# FlyballETS-SENSORS.net
KiCad netlist of a schematic drawn in EAGLE
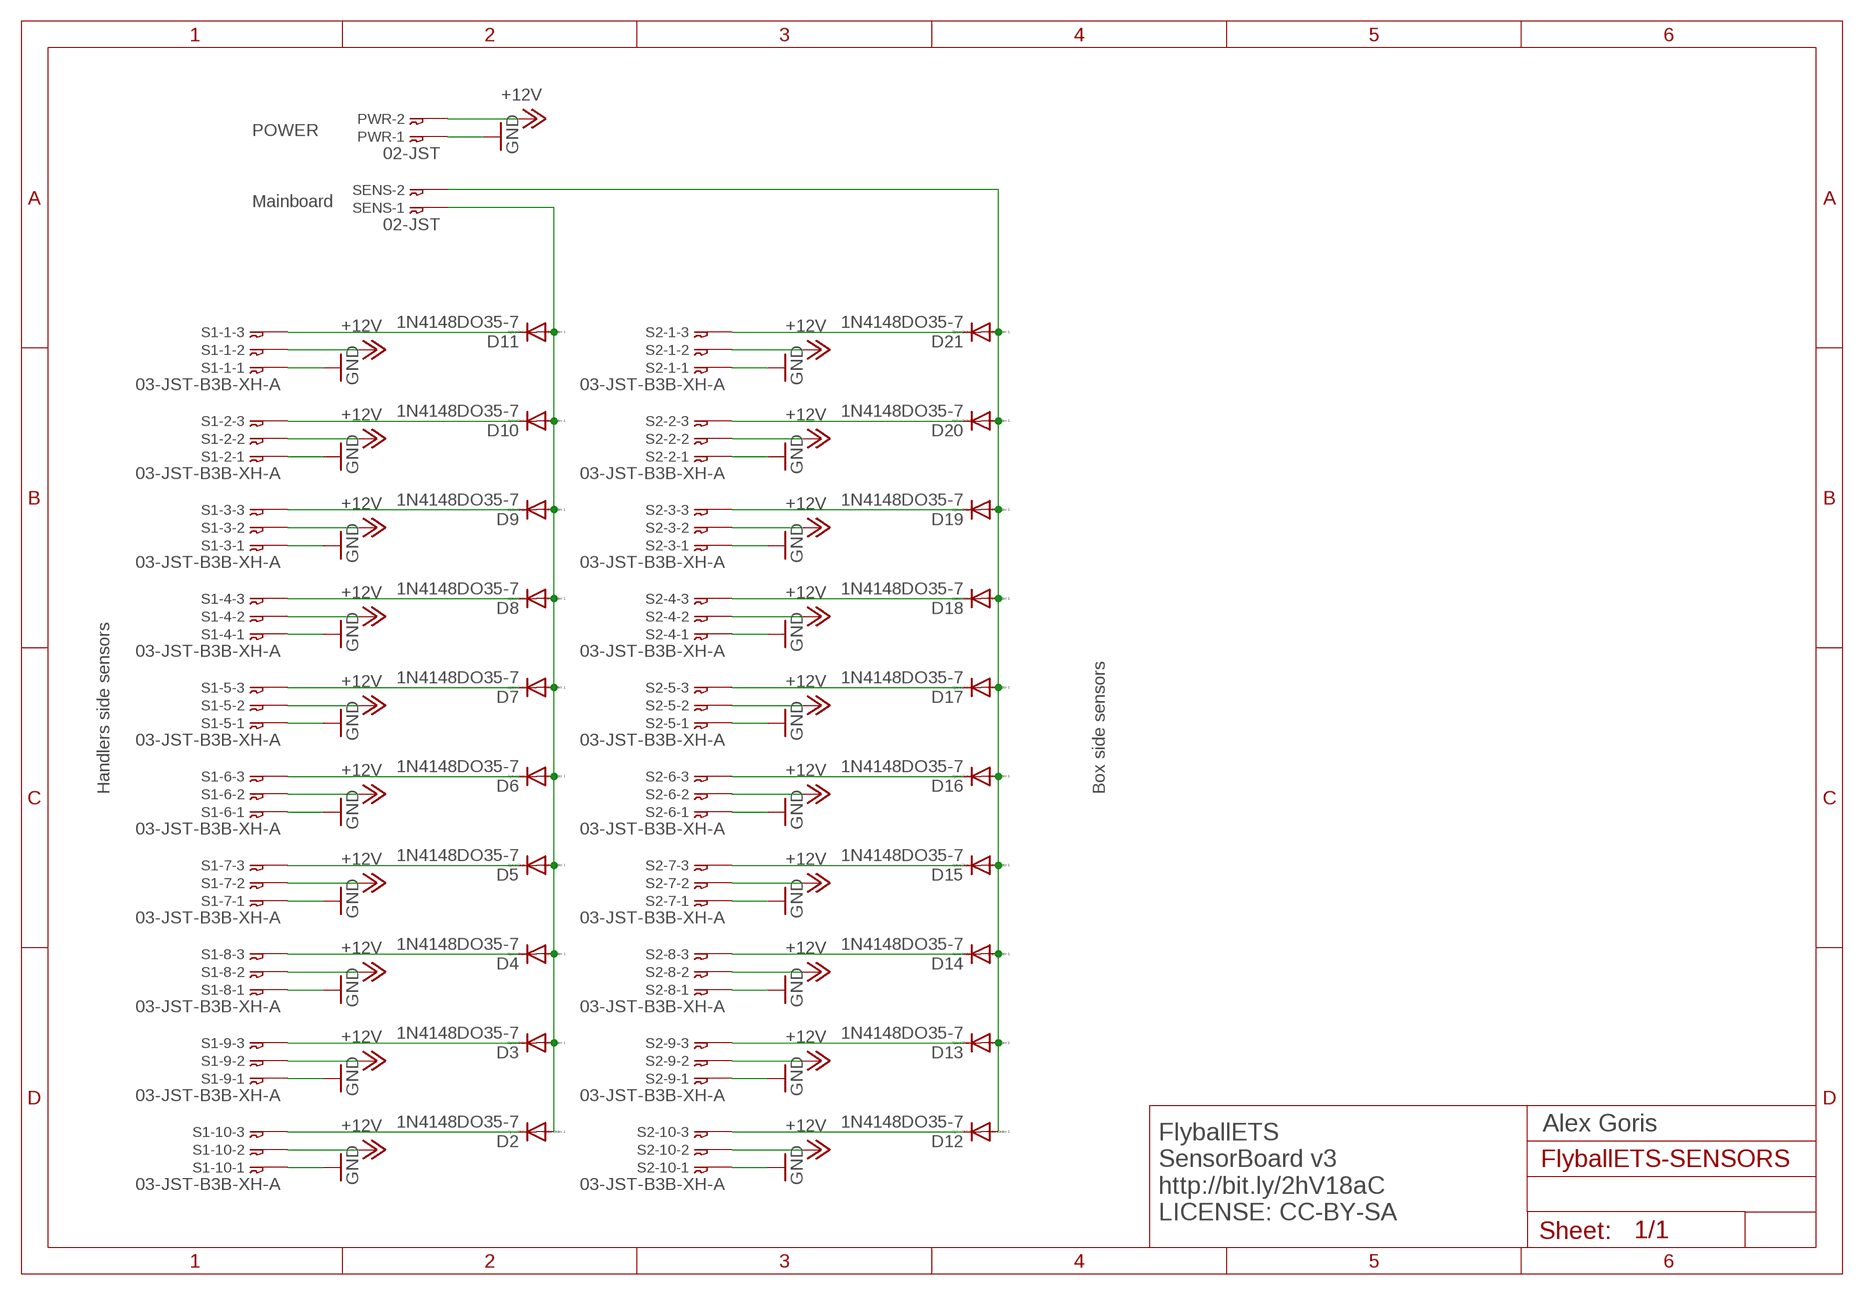
[diagram p0: schematic, sheet 1]

(export (version "E")
  (design (tool "Eeschema 10.0.6"))
  (components
    (comp (ref "D2")
      (value "1N4148DO35-7")
      (footprint "eagle-import:DO35-7")
      (libsource (lib "eagle-import") (part "1N4148DO35-7"))
    )
    (comp (ref "D3")
      (value "1N4148DO35-7")
      (footprint "eagle-import:DO35-7")
      (libsource (lib "eagle-import") (part "1N4148DO35-7"))
    )
    (comp (ref "D4")
      (value "1N4148DO35-7")
      (footprint "eagle-import:DO35-7")
      (libsource (lib "eagle-import") (part "1N4148DO35-7"))
    )
    (comp (ref "D5")
      (value "1N4148DO35-7")
      (footprint "eagle-import:DO35-7")
      (libsource (lib "eagle-import") (part "1N4148DO35-7"))
    )
    (comp (ref "D6")
      (value "1N4148DO35-7")
      (footprint "eagle-import:DO35-7")
      (libsource (lib "eagle-import") (part "1N4148DO35-7"))
    )
    (comp (ref "D7")
      (value "1N4148DO35-7")
      (footprint "eagle-import:DO35-7")
      (libsource (lib "eagle-import") (part "1N4148DO35-7"))
    )
    (comp (ref "D8")
      (value "1N4148DO35-7")
      (footprint "eagle-import:DO35-7")
      (libsource (lib "eagle-import") (part "1N4148DO35-7"))
    )
    (comp (ref "D9")
      (value "1N4148DO35-7")
      (footprint "eagle-import:DO35-7")
      (libsource (lib "eagle-import") (part "1N4148DO35-7"))
    )
    (comp (ref "D10")
      (value "1N4148DO35-7")
      (footprint "eagle-import:DO35-7")
      (libsource (lib "eagle-import") (part "1N4148DO35-7"))
    )
    (comp (ref "D11")
      (value "1N4148DO35-7")
      (footprint "eagle-import:DO35-7")
      (libsource (lib "eagle-import") (part "1N4148DO35-7"))
    )
    (comp (ref "D12")
      (value "1N4148DO35-7")
      (footprint "eagle-import:DO35-7")
      (libsource (lib "eagle-import") (part "1N4148DO35-7"))
    )
    (comp (ref "D13")
      (value "1N4148DO35-7")
      (footprint "eagle-import:DO35-7")
      (libsource (lib "eagle-import") (part "1N4148DO35-7"))
    )
    (comp (ref "D14")
      (value "1N4148DO35-7")
      (footprint "eagle-import:DO35-7")
      (libsource (lib "eagle-import") (part "1N4148DO35-7"))
    )
    (comp (ref "D15")
      (value "1N4148DO35-7")
      (footprint "eagle-import:DO35-7")
      (libsource (lib "eagle-import") (part "1N4148DO35-7"))
    )
    (comp (ref "D16")
      (value "1N4148DO35-7")
      (footprint "eagle-import:DO35-7")
      (libsource (lib "eagle-import") (part "1N4148DO35-7"))
    )
    (comp (ref "D17")
      (value "1N4148DO35-7")
      (footprint "eagle-import:DO35-7")
      (libsource (lib "eagle-import") (part "1N4148DO35-7"))
    )
    (comp (ref "D18")
      (value "1N4148DO35-7")
      (footprint "eagle-import:DO35-7")
      (libsource (lib "eagle-import") (part "1N4148DO35-7"))
    )
    (comp (ref "D19")
      (value "1N4148DO35-7")
      (footprint "eagle-import:DO35-7")
      (libsource (lib "eagle-import") (part "1N4148DO35-7"))
    )
    (comp (ref "D20")
      (value "1N4148DO35-7")
      (footprint "eagle-import:DO35-7")
      (libsource (lib "eagle-import") (part "1N4148DO35-7"))
    )
    (comp (ref "D21")
      (value "1N4148DO35-7")
      (footprint "eagle-import:DO35-7")
      (libsource (lib "eagle-import") (part "1N4148DO35-7"))
    )
    (comp (ref "PWR")
      (value "02-JST")
      (footprint "eagle-import:B2B-XH")
      (libsource (lib "eagle-import") (part "02-JST"))
    )
    (comp (ref "S1-1")
      (value "03-JST-B3B-XH-A")
      (footprint "eagle-import:B3B-XH")
      (libsource (lib "eagle-import") (part "03-JST-B3B-XH-A"))
    )
    (comp (ref "S1-2")
      (value "03-JST-B3B-XH-A")
      (footprint "eagle-import:B3B-XH")
      (libsource (lib "eagle-import") (part "03-JST-B3B-XH-A"))
    )
    (comp (ref "S1-3")
      (value "03-JST-B3B-XH-A")
      (footprint "eagle-import:B3B-XH")
      (libsource (lib "eagle-import") (part "03-JST-B3B-XH-A"))
    )
    (comp (ref "S1-4")
      (value "03-JST-B3B-XH-A")
      (footprint "eagle-import:B3B-XH")
      (libsource (lib "eagle-import") (part "03-JST-B3B-XH-A"))
    )
    (comp (ref "S1-5")
      (value "03-JST-B3B-XH-A")
      (footprint "eagle-import:B3B-XH")
      (libsource (lib "eagle-import") (part "03-JST-B3B-XH-A"))
    )
    (comp (ref "S1-6")
      (value "03-JST-B3B-XH-A")
      (footprint "eagle-import:B3B-XH")
      (libsource (lib "eagle-import") (part "03-JST-B3B-XH-A"))
    )
    (comp (ref "S1-7")
      (value "03-JST-B3B-XH-A")
      (footprint "eagle-import:B3B-XH")
      (libsource (lib "eagle-import") (part "03-JST-B3B-XH-A"))
    )
    (comp (ref "S1-8")
      (value "03-JST-B3B-XH-A")
      (footprint "eagle-import:B3B-XH")
      (libsource (lib "eagle-import") (part "03-JST-B3B-XH-A"))
    )
    (comp (ref "S1-9")
      (value "03-JST-B3B-XH-A")
      (footprint "eagle-import:B3B-XH")
      (libsource (lib "eagle-import") (part "03-JST-B3B-XH-A"))
    )
    (comp (ref "S1-10")
      (value "03-JST-B3B-XH-A")
      (footprint "eagle-import:B3B-XH")
      (libsource (lib "eagle-import") (part "03-JST-B3B-XH-A"))
    )
    (comp (ref "S2-1")
      (value "03-JST-B3B-XH-A")
      (footprint "eagle-import:B3B-XH")
      (libsource (lib "eagle-import") (part "03-JST-B3B-XH-A"))
    )
    (comp (ref "S2-2")
      (value "03-JST-B3B-XH-A")
      (footprint "eagle-import:B3B-XH")
      (libsource (lib "eagle-import") (part "03-JST-B3B-XH-A"))
    )
    (comp (ref "S2-3")
      (value "03-JST-B3B-XH-A")
      (footprint "eagle-import:B3B-XH")
      (libsource (lib "eagle-import") (part "03-JST-B3B-XH-A"))
    )
    (comp (ref "S2-4")
      (value "03-JST-B3B-XH-A")
      (footprint "eagle-import:B3B-XH")
      (libsource (lib "eagle-import") (part "03-JST-B3B-XH-A"))
    )
    (comp (ref "S2-5")
      (value "03-JST-B3B-XH-A")
      (footprint "eagle-import:B3B-XH")
      (libsource (lib "eagle-import") (part "03-JST-B3B-XH-A"))
    )
    (comp (ref "S2-6")
      (value "03-JST-B3B-XH-A")
      (footprint "eagle-import:B3B-XH")
      (libsource (lib "eagle-import") (part "03-JST-B3B-XH-A"))
    )
    (comp (ref "S2-7")
      (value "03-JST-B3B-XH-A")
      (footprint "eagle-import:B3B-XH")
      (libsource (lib "eagle-import") (part "03-JST-B3B-XH-A"))
    )
    (comp (ref "S2-8")
      (value "03-JST-B3B-XH-A")
      (footprint "eagle-import:B3B-XH")
      (libsource (lib "eagle-import") (part "03-JST-B3B-XH-A"))
    )
    (comp (ref "S2-9")
      (value "03-JST-B3B-XH-A")
      (footprint "eagle-import:B3B-XH")
      (libsource (lib "eagle-import") (part "03-JST-B3B-XH-A"))
    )
    (comp (ref "S2-10")
      (value "03-JST-B3B-XH-A")
      (footprint "eagle-import:B3B-XH")
      (libsource (lib "eagle-import") (part "03-JST-B3B-XH-A"))
    )
    (comp (ref "SENS")
      (value "02-JST")
      (footprint "eagle-import:B2B-XH")
      (libsource (lib "eagle-import") (part "02-JST"))
    )
  )
  (nets
    (net (code "1") (name "+12V") (class "Default")
      (node (ref "PWR") (pin "P$2") (pinfunction "1_P$2") (pintype "passive"))
      (node (ref "S1-1") (pin "P$2") (pinfunction "1_P$2") (pintype "passive"))
      (node (ref "S1-10") (pin "P$2") (pinfunction "1_P$2") (pintype "passive"))
      (node (ref "S1-2") (pin "P$2") (pinfunction "1_P$2") (pintype "passive"))
      (node (ref "S1-3") (pin "P$2") (pinfunction "1_P$2") (pintype "passive"))
      (node (ref "S1-4") (pin "P$2") (pinfunction "1_P$2") (pintype "passive"))
      (node (ref "S1-5") (pin "P$2") (pinfunction "1_P$2") (pintype "passive"))
      (node (ref "S1-6") (pin "P$2") (pinfunction "1_P$2") (pintype "passive"))
      (node (ref "S1-7") (pin "P$2") (pinfunction "1_P$2") (pintype "passive"))
      (node (ref "S1-8") (pin "P$2") (pinfunction "1_P$2") (pintype "passive"))
      (node (ref "S1-9") (pin "P$2") (pinfunction "1_P$2") (pintype "passive"))
      (node (ref "S2-1") (pin "P$2") (pinfunction "1_P$2") (pintype "passive"))
      (node (ref "S2-10") (pin "P$2") (pinfunction "1_P$2") (pintype "passive"))
      (node (ref "S2-2") (pin "P$2") (pinfunction "1_P$2") (pintype "passive"))
      (node (ref "S2-3") (pin "P$2") (pinfunction "1_P$2") (pintype "passive"))
      (node (ref "S2-4") (pin "P$2") (pinfunction "1_P$2") (pintype "passive"))
      (node (ref "S2-5") (pin "P$2") (pinfunction "1_P$2") (pintype "passive"))
      (node (ref "S2-6") (pin "P$2") (pinfunction "1_P$2") (pintype "passive"))
      (node (ref "S2-7") (pin "P$2") (pinfunction "1_P$2") (pintype "passive"))
      (node (ref "S2-8") (pin "P$2") (pinfunction "1_P$2") (pintype "passive"))
      (node (ref "S2-9") (pin "P$2") (pinfunction "1_P$2") (pintype "passive"))
    )
    (net (code "2") (name "GND") (class "Default")
      (node (ref "PWR") (pin "P$1") (pinfunction "1_P$1") (pintype "passive"))
      (node (ref "S1-1") (pin "P$1") (pinfunction "1_P$1") (pintype "passive"))
      (node (ref "S1-10") (pin "P$1") (pinfunction "1_P$1") (pintype "passive"))
      (node (ref "S1-2") (pin "P$1") (pinfunction "1_P$1") (pintype "passive"))
      (node (ref "S1-3") (pin "P$1") (pinfunction "1_P$1") (pintype "passive"))
      (node (ref "S1-4") (pin "P$1") (pinfunction "1_P$1") (pintype "passive"))
      (node (ref "S1-5") (pin "P$1") (pinfunction "1_P$1") (pintype "passive"))
      (node (ref "S1-6") (pin "P$1") (pinfunction "1_P$1") (pintype "passive"))
      (node (ref "S1-7") (pin "P$1") (pinfunction "1_P$1") (pintype "passive"))
      (node (ref "S1-8") (pin "P$1") (pinfunction "1_P$1") (pintype "passive"))
      (node (ref "S1-9") (pin "P$1") (pinfunction "1_P$1") (pintype "passive"))
      (node (ref "S2-1") (pin "P$1") (pinfunction "1_P$1") (pintype "passive"))
      (node (ref "S2-10") (pin "P$1") (pinfunction "1_P$1") (pintype "passive"))
      (node (ref "S2-2") (pin "P$1") (pinfunction "1_P$1") (pintype "passive"))
      (node (ref "S2-3") (pin "P$1") (pinfunction "1_P$1") (pintype "passive"))
      (node (ref "S2-4") (pin "P$1") (pinfunction "1_P$1") (pintype "passive"))
      (node (ref "S2-5") (pin "P$1") (pinfunction "1_P$1") (pintype "passive"))
      (node (ref "S2-6") (pin "P$1") (pinfunction "1_P$1") (pintype "passive"))
      (node (ref "S2-7") (pin "P$1") (pinfunction "1_P$1") (pintype "passive"))
      (node (ref "S2-8") (pin "P$1") (pinfunction "1_P$1") (pintype "passive"))
      (node (ref "S2-9") (pin "P$1") (pinfunction "1_P$1") (pintype "passive"))
    )
    (net (code "3") (name "Net-(S1-1C-1)") (class "Default")
      (node (ref "D11") (pin "C") (pinfunction "C_C") (pintype "passive"))
      (node (ref "S1-1") (pin "P$3") (pinfunction "1_P$3") (pintype "passive"))
    )
    (net (code "4") (name "Net-(S1-2C-1)") (class "Default")
      (node (ref "D10") (pin "C") (pinfunction "C_C") (pintype "passive"))
      (node (ref "S1-2") (pin "P$3") (pinfunction "1_P$3") (pintype "passive"))
    )
    (net (code "5") (name "Net-(S1-3C-1)") (class "Default")
      (node (ref "D9") (pin "C") (pinfunction "C_C") (pintype "passive"))
      (node (ref "S1-3") (pin "P$3") (pinfunction "1_P$3") (pintype "passive"))
    )
    (net (code "6") (name "Net-(S1-4C-1)") (class "Default")
      (node (ref "D8") (pin "C") (pinfunction "C_C") (pintype "passive"))
      (node (ref "S1-4") (pin "P$3") (pinfunction "1_P$3") (pintype "passive"))
    )
    (net (code "7") (name "Net-(S1-5C-1)") (class "Default")
      (node (ref "D7") (pin "C") (pinfunction "C_C") (pintype "passive"))
      (node (ref "S1-5") (pin "P$3") (pinfunction "1_P$3") (pintype "passive"))
    )
    (net (code "8") (name "Net-(S1-6C-1)") (class "Default")
      (node (ref "D6") (pin "C") (pinfunction "C_C") (pintype "passive"))
      (node (ref "S1-6") (pin "P$3") (pinfunction "1_P$3") (pintype "passive"))
    )
    (net (code "9") (name "Net-(S1-7C-1)") (class "Default")
      (node (ref "D5") (pin "C") (pinfunction "C_C") (pintype "passive"))
      (node (ref "S1-7") (pin "P$3") (pinfunction "1_P$3") (pintype "passive"))
    )
    (net (code "10") (name "Net-(S1-8C-1)") (class "Default")
      (node (ref "D4") (pin "C") (pinfunction "C_C") (pintype "passive"))
      (node (ref "S1-8") (pin "P$3") (pinfunction "1_P$3") (pintype "passive"))
    )
    (net (code "11") (name "Net-(S1-9C-1)") (class "Default")
      (node (ref "D3") (pin "C") (pinfunction "C_C") (pintype "passive"))
      (node (ref "S1-9") (pin "P$3") (pinfunction "1_P$3") (pintype "passive"))
    )
    (net (code "12") (name "Net-(S1-10C-1)") (class "Default")
      (node (ref "D2") (pin "C") (pinfunction "C_C") (pintype "passive"))
      (node (ref "S1-10") (pin "P$3") (pinfunction "1_P$3") (pintype "passive"))
    )
    (net (code "13") (name "Net-(S2-1C-1)") (class "Default")
      (node (ref "D21") (pin "C") (pinfunction "C_C") (pintype "passive"))
      (node (ref "S2-1") (pin "P$3") (pinfunction "1_P$3") (pintype "passive"))
    )
    (net (code "14") (name "Net-(S2-2C-1)") (class "Default")
      (node (ref "D20") (pin "C") (pinfunction "C_C") (pintype "passive"))
      (node (ref "S2-2") (pin "P$3") (pinfunction "1_P$3") (pintype "passive"))
    )
    (net (code "15") (name "Net-(S2-3C-1)") (class "Default")
      (node (ref "D19") (pin "C") (pinfunction "C_C") (pintype "passive"))
      (node (ref "S2-3") (pin "P$3") (pinfunction "1_P$3") (pintype "passive"))
    )
    (net (code "16") (name "Net-(S2-4C-1)") (class "Default")
      (node (ref "D18") (pin "C") (pinfunction "C_C") (pintype "passive"))
      (node (ref "S2-4") (pin "P$3") (pinfunction "1_P$3") (pintype "passive"))
    )
    (net (code "17") (name "Net-(S2-5C-1)") (class "Default")
      (node (ref "D17") (pin "C") (pinfunction "C_C") (pintype "passive"))
      (node (ref "S2-5") (pin "P$3") (pinfunction "1_P$3") (pintype "passive"))
    )
    (net (code "18") (name "Net-(S2-6C-1)") (class "Default")
      (node (ref "D16") (pin "C") (pinfunction "C_C") (pintype "passive"))
      (node (ref "S2-6") (pin "P$3") (pinfunction "1_P$3") (pintype "passive"))
    )
    (net (code "19") (name "Net-(S2-7C-1)") (class "Default")
      (node (ref "D15") (pin "C") (pinfunction "C_C") (pintype "passive"))
      (node (ref "S2-7") (pin "P$3") (pinfunction "1_P$3") (pintype "passive"))
    )
    (net (code "20") (name "Net-(S2-8C-1)") (class "Default")
      (node (ref "D14") (pin "C") (pinfunction "C_C") (pintype "passive"))
      (node (ref "S2-8") (pin "P$3") (pinfunction "1_P$3") (pintype "passive"))
    )
    (net (code "21") (name "Net-(S2-9C-1)") (class "Default")
      (node (ref "D13") (pin "C") (pinfunction "C_C") (pintype "passive"))
      (node (ref "S2-9") (pin "P$3") (pinfunction "1_P$3") (pintype "passive"))
    )
    (net (code "22") (name "Net-(S2-10C-1)") (class "Default")
      (node (ref "D12") (pin "C") (pinfunction "C_C") (pintype "passive"))
      (node (ref "S2-10") (pin "P$3") (pinfunction "1_P$3") (pintype "passive"))
    )
    (net (code "23") (name "Net-(SENSA-1)") (class "Default")
      (node (ref "D10") (pin "A") (pinfunction "A_A") (pintype "passive"))
      (node (ref "D11") (pin "A") (pinfunction "A_A") (pintype "passive"))
      (node (ref "D2") (pin "A") (pinfunction "A_A") (pintype "passive"))
      (node (ref "D3") (pin "A") (pinfunction "A_A") (pintype "passive"))
      (node (ref "D4") (pin "A") (pinfunction "A_A") (pintype "passive"))
      (node (ref "D5") (pin "A") (pinfunction "A_A") (pintype "passive"))
      (node (ref "D6") (pin "A") (pinfunction "A_A") (pintype "passive"))
      (node (ref "D7") (pin "A") (pinfunction "A_A") (pintype "passive"))
      (node (ref "D8") (pin "A") (pinfunction "A_A") (pintype "passive"))
      (node (ref "D9") (pin "A") (pinfunction "A_A") (pintype "passive"))
      (node (ref "SENS") (pin "P$1") (pinfunction "1_P$1") (pintype "passive"))
    )
    (net (code "24") (name "Net-(SENSB-1)") (class "Default")
      (node (ref "D12") (pin "A") (pinfunction "A_A") (pintype "passive"))
      (node (ref "D13") (pin "A") (pinfunction "A_A") (pintype "passive"))
      (node (ref "D14") (pin "A") (pinfunction "A_A") (pintype "passive"))
      (node (ref "D15") (pin "A") (pinfunction "A_A") (pintype "passive"))
      (node (ref "D16") (pin "A") (pinfunction "A_A") (pintype "passive"))
      (node (ref "D17") (pin "A") (pinfunction "A_A") (pintype "passive"))
      (node (ref "D18") (pin "A") (pinfunction "A_A") (pintype "passive"))
      (node (ref "D19") (pin "A") (pinfunction "A_A") (pintype "passive"))
      (node (ref "D20") (pin "A") (pinfunction "A_A") (pintype "passive"))
      (node (ref "D21") (pin "A") (pinfunction "A_A") (pintype "passive"))
      (node (ref "SENS") (pin "P$2") (pinfunction "1_P$2") (pintype "passive"))
    )
  )
)
